# BMP384_Breakout.net
KiCad netlist of a schematic drawn in EAGLE
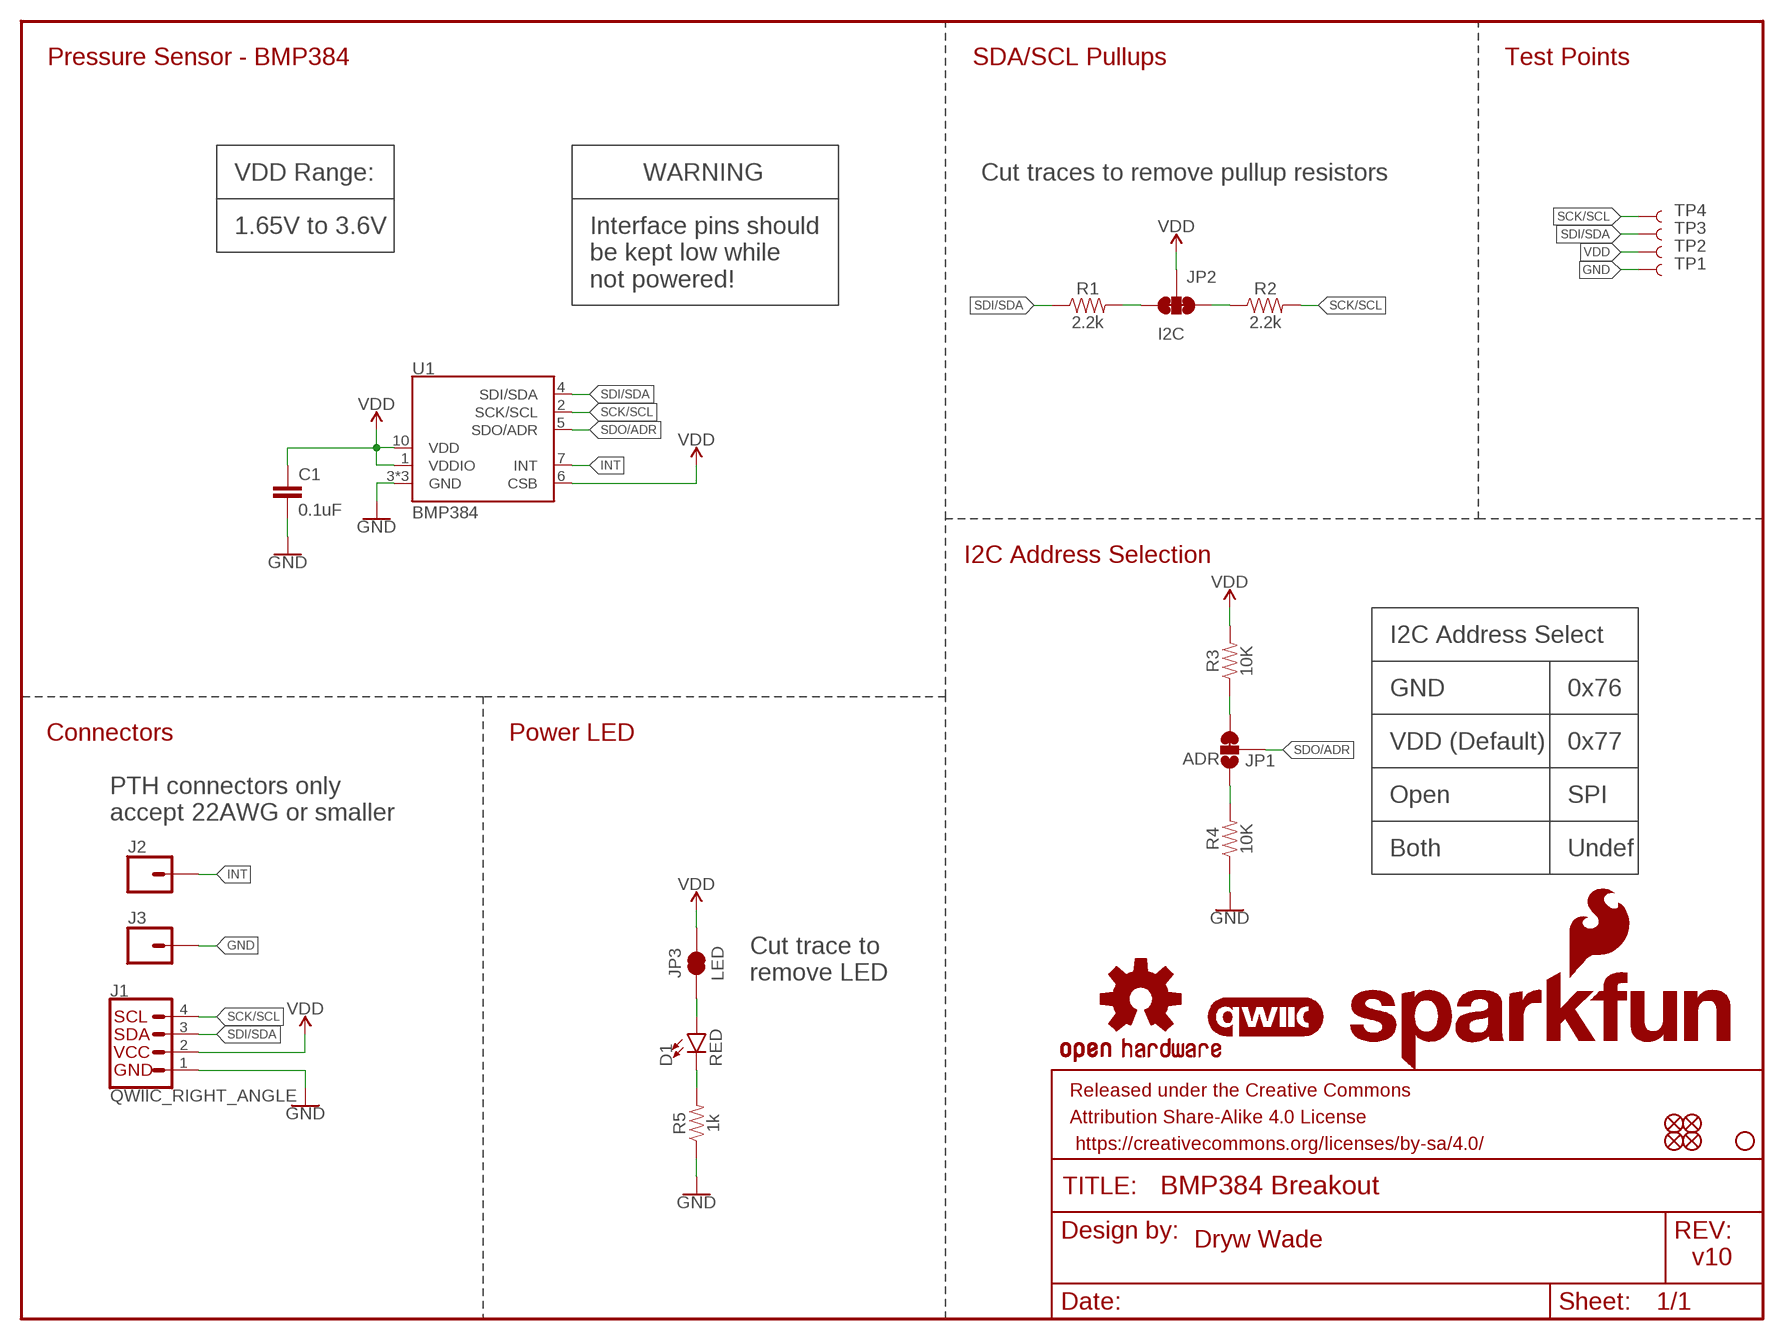
[diagram p0: schematic, sheet 1]

(export (version "E")
  (design (tool "Eeschema 10.0.6"))
  (components
    (comp (ref "C1")
      (value "0.1uF")
      (footprint "eagle-import:0402-TIGHT")
      (libsource (lib "eagle-import") (part "0.1UF-0402T-6.3V-10%-X7R"))
    )
    (comp (ref "D1")
      (value "RED")
      (footprint "eagle-import:LED-0402")
      (libsource (lib "eagle-import") (part "LED-RED_0402"))
    )
    (comp (ref "FD1")
      (value "FIDUCIALUFIDUCIAL")
      (footprint "eagle-import:FIDUCIAL-MICRO")
      (libsource (lib "eagle-import") (part "FIDUCIALUFIDUCIAL"))
    )
    (comp (ref "FD2")
      (value "FIDUCIALUFIDUCIAL")
      (footprint "eagle-import:FIDUCIAL-MICRO")
      (libsource (lib "eagle-import") (part "FIDUCIALUFIDUCIAL"))
    )
    (comp (ref "FD3")
      (value "FIDUCIALUFIDUCIAL")
      (footprint "eagle-import:FIDUCIAL-MICRO")
      (libsource (lib "eagle-import") (part "FIDUCIALUFIDUCIAL"))
    )
    (comp (ref "FD4")
      (value "FIDUCIALUFIDUCIAL")
      (footprint "eagle-import:FIDUCIAL-MICRO")
      (libsource (lib "eagle-import") (part "FIDUCIALUFIDUCIAL"))
    )
    (comp (ref "FRAME1")
      (value "FRAME-LETTER")
      (footprint "eagle-import:CREATIVE_COMMONS")
      (libsource (lib "eagle-import") (part "FRAME-LETTER"))
    )
    (comp (ref "H1")
      (value "STAND-OFF")
      (footprint "eagle-import:STAND-OFF")
      (libsource (lib "eagle-import") (part "STAND-OFF"))
    )
    (comp (ref "J1")
      (value "QWIIC_RIGHT_ANGLE")
      (footprint "eagle-import:JST04_1MM_RA")
      (libsource (lib "eagle-import") (part "QWIIC_CONNECTORJS-1MM"))
    )
    (comp (ref "J2")
      (value "CONN_01_1MM")
      (footprint "eagle-import:1X01_1MM_NO_SILK")
      (libsource (lib "eagle-import") (part "CONN_01_1MM"))
    )
    (comp (ref "J3")
      (value "CONN_01_1MM")
      (footprint "eagle-import:1X01_1MM_NO_SILK")
      (libsource (lib "eagle-import") (part "CONN_01_1MM"))
    )
    (comp (ref "JP1")
      (value "ADR")
      (footprint "eagle-import:SMT-JUMPER_3_1-NC_TRACE_SILK")
      (libsource (lib "eagle-import") (part "JUMPER-SMT_3_1-NC_TRACE_SILK"))
    )
    (comp (ref "JP2")
      (value "I2C")
      (footprint "eagle-import:SMT-JUMPER_3_2-NC_TRACE_SILK")
      (libsource (lib "eagle-import") (part "JUMPER-SMT_3_2-NC_TRACE_SILK"))
    )
    (comp (ref "JP3")
      (value "LED")
      (footprint "eagle-import:SMT-JUMPER_2_NC_TRACE_SILK")
      (libsource (lib "eagle-import") (part "JUMPER-SMT_2_NC_TRACE_SILK"))
    )
    (comp (ref "LOGO1")
      (value "SFE_LOGO_FLAME.1_INCH")
      (footprint "eagle-import:SFE_LOGO_FLAME_.1")
      (libsource (lib "eagle-import") (part "SFE_LOGO_FLAME.1_INCH"))
    )
    (comp (ref "LOGO2")
      (value "QWIIC_LOGO_3MM")
      (footprint "eagle-import:QWIIC_3MM")
      (libsource (lib "eagle-import") (part "QWIIC_LOGO_3MM"))
    )
    (comp (ref "LOGO3")
      (value "OSHW-LOGOMINI")
      (footprint "eagle-import:OSHW-LOGO-MINI")
      (libsource (lib "eagle-import") (part "OSHW-LOGOMINI"))
    )
    (comp (ref "LOGO4")
      (value "SFE_LOGO_NAMEBLANK")
      (footprint "eagle-import:BLANK")
      (libsource (lib "eagle-import") (part "SFE_LOGO_NAMEBLANK"))
    )
    (comp (ref "R1")
      (value "2.2k")
      (footprint "eagle-import:0402-TIGHT")
      (libsource (lib "eagle-import") (part "2.2KOHM-0402T-1/16W-1%"))
    )
    (comp (ref "R2")
      (value "2.2k")
      (footprint "eagle-import:0402-TIGHT")
      (libsource (lib "eagle-import") (part "2.2KOHM-0402T-1/16W-1%"))
    )
    (comp (ref "R3")
      (value "10K")
      (footprint "eagle-import:0402-TIGHT")
      (libsource (lib "eagle-import") (part "10KOHM-0402-1/10W-0.1%"))
    )
    (comp (ref "R4")
      (value "10K")
      (footprint "eagle-import:0402-TIGHT")
      (libsource (lib "eagle-import") (part "10KOHM-0402-1/10W-0.1%"))
    )
    (comp (ref "R5")
      (value "1k")
      (footprint "eagle-import:0402-TIGHT")
      (libsource (lib "eagle-import") (part "1KOHM-0402T-1/16W-1%"))
    )
    (comp (ref "TP1")
      (value "TEST-POINT3")
      (footprint "eagle-import:PAD.03X.03")
      (libsource (lib "eagle-import") (part "TEST-POINT3"))
    )
    (comp (ref "TP2")
      (value "TEST-POINT3")
      (footprint "eagle-import:PAD.03X.03")
      (libsource (lib "eagle-import") (part "TEST-POINT3"))
    )
    (comp (ref "TP3")
      (value "TEST-POINT3")
      (footprint "eagle-import:PAD.03X.03")
      (libsource (lib "eagle-import") (part "TEST-POINT3"))
    )
    (comp (ref "TP4")
      (value "TEST-POINT3")
      (footprint "eagle-import:PAD.03X.03")
      (libsource (lib "eagle-import") (part "TEST-POINT3"))
    )
    (comp (ref "U1")
      (value "BMP384")
      (footprint "eagle-import:LGA-10")
      (libsource (lib "eagle-import") (part "BMP384"))
    )
  )
  (nets
    (net (code "1") (name "GND") (class "Default")
      (node (ref "C1") (pin "2") (pinfunction "2_2") (pintype "passive"))
      (node (ref "J1") (pin "1") (pinfunction "1_1") (pintype "power_in"))
      (node (ref "J3") (pin "1") (pinfunction "1_1") (pintype "passive"))
      (node (ref "R4") (pin "1") (pinfunction "1_1") (pintype "passive"))
      (node (ref "R5") (pin "1") (pinfunction "1_1") (pintype "passive"))
      (node (ref "TP1") (pin "1") (pinfunction "1_1") (pintype "bidirectional"))
      (node (ref "U1") (pin "3") (pinfunction "GND_3") (pintype "power_in"))
      (node (ref "U1") (pin "8") (pinfunction "GND_8") (pintype "power_in"))
      (node (ref "U1") (pin "9") (pinfunction "GND_9") (pintype "power_in"))
    )
    (net (code "2") (name "INT") (class "Default")
      (node (ref "J2") (pin "1") (pinfunction "1_1") (pintype "passive"))
      (node (ref "U1") (pin "7") (pinfunction "INT_7") (pintype "output"))
    )
    (net (code "3") (name "Net-(D1-PadA)") (class "Default")
      (node (ref "D1") (pin "A") (pinfunction "A_A") (pintype "passive"))
      (node (ref "JP3") (pin "1") (pinfunction "1_1") (pintype "passive"))
    )
    (net (code "4") (name "Net-(D1-PadC)") (class "Default")
      (node (ref "D1") (pin "C") (pinfunction "C_C") (pintype "passive"))
      (node (ref "R5") (pin "2") (pinfunction "2_2") (pintype "passive"))
    )
    (net (code "5") (name "Net-(JP1-Pad1)") (class "Default")
      (node (ref "JP1") (pin "1") (pinfunction "1_1") (pintype "passive"))
      (node (ref "R4") (pin "2") (pinfunction "2_2") (pintype "passive"))
    )
    (net (code "6") (name "Net-(JP1-Pad3)") (class "Default")
      (node (ref "JP1") (pin "3") (pinfunction "3_3") (pintype "passive"))
      (node (ref "R3") (pin "1") (pinfunction "1_1") (pintype "passive"))
    )
    (net (code "7") (name "Net-(JP2-Pad1)") (class "Default")
      (node (ref "JP2") (pin "1") (pinfunction "1_1") (pintype "passive"))
      (node (ref "R2") (pin "1") (pinfunction "1_1") (pintype "passive"))
    )
    (net (code "8") (name "Net-(JP2-Pad3)") (class "Default")
      (node (ref "JP2") (pin "3") (pinfunction "3_3") (pintype "passive"))
      (node (ref "R1") (pin "2") (pinfunction "2_2") (pintype "passive"))
    )
    (net (code "9") (name "SCK{slash}SCL") (class "Default")
      (node (ref "J1") (pin "4") (pinfunction "4_4") (pintype "passive"))
      (node (ref "R2") (pin "2") (pinfunction "2_2") (pintype "passive"))
      (node (ref "TP4") (pin "1") (pinfunction "1_1") (pintype "bidirectional"))
      (node (ref "U1") (pin "2") (pinfunction "SCK/SCL_2") (pintype "bidirectional"))
    )
    (net (code "10") (name "SDI{slash}SDA") (class "Default")
      (node (ref "J1") (pin "3") (pinfunction "3_3") (pintype "passive"))
      (node (ref "R1") (pin "1") (pinfunction "1_1") (pintype "passive"))
      (node (ref "TP3") (pin "1") (pinfunction "1_1") (pintype "bidirectional"))
      (node (ref "U1") (pin "4") (pinfunction "SDI/SDA_4") (pintype "bidirectional"))
    )
    (net (code "11") (name "SDO{slash}ADR") (class "Default")
      (node (ref "JP1") (pin "2") (pinfunction "2_2") (pintype "passive"))
      (node (ref "U1") (pin "5") (pinfunction "SDO/ADR_5") (pintype "bidirectional"))
    )
    (net (code "12") (name "VDD") (class "Default")
      (node (ref "C1") (pin "1") (pinfunction "1_1") (pintype "passive"))
      (node (ref "J1") (pin "2") (pinfunction "2_2") (pintype "power_in"))
      (node (ref "JP2") (pin "2") (pinfunction "2_2") (pintype "passive"))
      (node (ref "JP3") (pin "2") (pinfunction "2_2") (pintype "passive"))
      (node (ref "R3") (pin "2") (pinfunction "2_2") (pintype "passive"))
      (node (ref "TP2") (pin "1") (pinfunction "1_1") (pintype "bidirectional"))
      (node (ref "U1") (pin "1") (pinfunction "VDDIO_1") (pintype "power_in"))
      (node (ref "U1") (pin "10") (pinfunction "VDD_10") (pintype "power_in"))
      (node (ref "U1") (pin "6") (pinfunction "CSB_6") (pintype "input"))
    )
  )
)
